# LCLFilter_Top.net
KiCad netlist of a schematic drawn in Altium Designer
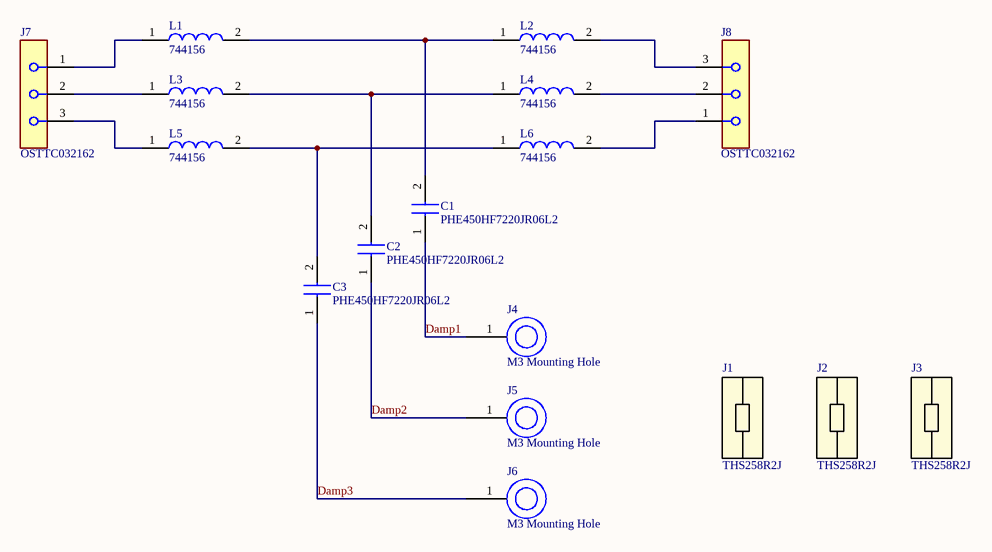
[diagram p0: LCLFilter_Top.SchDoc]

(export (version "E")
  (design (tool "Eeschema 10.0.6"))
  (components
    (comp (ref "C1")
      (value "PHE450HF7220JR06L2")
      (footprint "Film Capacitor PHE450HF7220JR06L2")
      (description "Capacitor")
      (libsource (lib "FYP_Components") (part "PHE450HF7220JR06L2"))
    )
    (comp (ref "C2")
      (value "PHE450HF7220JR06L2")
      (footprint "Film Capacitor PHE450HF7220JR06L2")
      (description "Capacitor")
      (libsource (lib "FYP_Components") (part "PHE450HF7220JR06L2"))
    )
    (comp (ref "C3")
      (value "PHE450HF7220JR06L2")
      (footprint "Film Capacitor PHE450HF7220JR06L2")
      (description "Capacitor")
      (libsource (lib "FYP_Components") (part "PHE450HF7220JR06L2"))
    )
    (comp (ref "J1")
      (value "THS258R2J")
      (footprint "Resistor CONN2_ THS258R2J_TEC")
      (description "Resistor, Axial Leaded, 8.2 ohm, THS, 25 W, ± 5%, Solder Lug, 550 V")
      (fields (field (name "COPYRIGHT") "Copyright (C) 2023 Ultra Librarian. All rights reserved."))
      (libsource (lib "FYP_Components") (part "THS258R2J"))
    )
    (comp (ref "J2")
      (value "THS258R2J")
      (footprint "Resistor CONN2_ THS258R2J_TEC")
      (description "Resistor, Axial Leaded, 8.2 ohm, THS, 25 W, ± 5%, Solder Lug, 550 V")
      (fields (field (name "COPYRIGHT") "Copyright (C) 2023 Ultra Librarian. All rights reserved."))
      (libsource (lib "FYP_Components") (part "THS258R2J"))
    )
    (comp (ref "J3")
      (value "THS258R2J")
      (footprint "Resistor CONN2_ THS258R2J_TEC")
      (description "Resistor, Axial Leaded, 8.2 ohm, THS, 25 W, ± 5%, Solder Lug, 550 V")
      (fields (field (name "COPYRIGHT") "Copyright (C) 2023 Ultra Librarian. All rights reserved."))
      (libsource (lib "FYP_Components") (part "THS258R2J"))
    )
    (comp (ref "J4")
      (value "M3 Mounting Hole")
      (footprint "M3 Mounting Hole")
      (libsource (lib "FYP_Components") (part "M3 Mounting Hole"))
    )
    (comp (ref "J5")
      (value "M3 Mounting Hole")
      (footprint "M3 Mounting Hole")
      (libsource (lib "FYP_Components") (part "M3 Mounting Hole"))
    )
    (comp (ref "J6")
      (value "M3 Mounting Hole")
      (footprint "M3 Mounting Hole")
      (libsource (lib "FYP_Components") (part "M3 Mounting Hole"))
    )
    (comp (ref "J7")
      (value "OSTTC032162")
      (footprint "3 Pin Terminal OSTTC032162_0")
      (description "3 Position Terminal Block 5.08mm")
      (fields
        (field (name "VOLTAGE") "300V")
        (field (name "MANUFACTURER") "On Shore Technology")
        (field (name "PART NUMBER") "OSTTC032162")
      )
      (libsource (lib "FYP_Components") (part "OSTTC032162"))
    )
    (comp (ref "J8")
      (value "OSTTC032162")
      (footprint "3 Pin Terminal OSTTC032162_0")
      (description "3 Position Terminal Block 5.08mm")
      (fields
        (field (name "VOLTAGE") "300V")
        (field (name "MANUFACTURER") "On Shore Technology")
        (field (name "PART NUMBER") "OSTTC032162")
      )
      (libsource (lib "") (part "OSTTC032162_1"))
    )
    (comp (ref "L1")
      (value "744156")
      (footprint "Toroid Inductor 744156")
      (description "Toroidal Inductor, WE-SI, 380 µH, 6.2 A, 0.07 ohm, ± 20%")
      (libsource (lib "FYP_Components") (part "744156"))
    )
    (comp (ref "L2")
      (value "744156")
      (footprint "Toroid Inductor 744156")
      (description "Toroidal Inductor, WE-SI, 380 µH, 6.2 A, 0.07 ohm, ± 20%")
      (libsource (lib "FYP_Components") (part "744156"))
    )
    (comp (ref "L3")
      (value "744156")
      (footprint "Toroid Inductor 744156")
      (description "Toroidal Inductor, WE-SI, 380 µH, 6.2 A, 0.07 ohm, ± 20%")
      (libsource (lib "FYP_Components") (part "744156"))
    )
    (comp (ref "L4")
      (value "744156")
      (footprint "Toroid Inductor 744156")
      (description "Toroidal Inductor, WE-SI, 380 µH, 6.2 A, 0.07 ohm, ± 20%")
      (libsource (lib "FYP_Components") (part "744156"))
    )
    (comp (ref "L5")
      (value "744156")
      (footprint "Toroid Inductor 744156")
      (description "Toroidal Inductor, WE-SI, 380 µH, 6.2 A, 0.07 ohm, ± 20%")
      (libsource (lib "FYP_Components") (part "744156"))
    )
    (comp (ref "L6")
      (value "744156")
      (footprint "Toroid Inductor 744156")
      (description "Toroidal Inductor, WE-SI, 380 µH, 6.2 A, 0.07 ohm, ± 20%")
      (libsource (lib "FYP_Components") (part "744156"))
    )
  )
  (nets
    (net (code "1") (name "/Damp1") (class "Default")
      (node (ref "C1") (pin "1") (pinfunction "1_1") (pintype "passive"))
      (node (ref "J4") (pin "1") (pinfunction "1_1") (pintype "passive"))
    )
    (net (code "2") (name "/Damp2") (class "Default")
      (node (ref "C2") (pin "1") (pinfunction "1_1") (pintype "passive"))
      (node (ref "J5") (pin "1") (pinfunction "1_1") (pintype "passive"))
    )
    (net (code "3") (name "/Damp3") (class "Default")
      (node (ref "C3") (pin "1") (pinfunction "1_1") (pintype "passive"))
      (node (ref "J6") (pin "1") (pinfunction "1_1") (pintype "passive"))
    )
    (net (code "4") (name "Net-(C1-Pad2)") (class "Default")
      (node (ref "C1") (pin "2") (pinfunction "2_2") (pintype "passive"))
      (node (ref "L1") (pin "2") (pinfunction "2_2") (pintype "passive"))
      (node (ref "L2") (pin "1") (pinfunction "1_1") (pintype "passive"))
    )
    (net (code "5") (name "Net-(C2-Pad2)") (class "Default")
      (node (ref "C2") (pin "2") (pinfunction "2_2") (pintype "passive"))
      (node (ref "L3") (pin "2") (pinfunction "2_2") (pintype "passive"))
      (node (ref "L4") (pin "1") (pinfunction "1_1") (pintype "passive"))
    )
    (net (code "6") (name "Net-(C3-Pad2)") (class "Default")
      (node (ref "C3") (pin "2") (pinfunction "2_2") (pintype "passive"))
      (node (ref "L5") (pin "2") (pinfunction "2_2") (pintype "passive"))
      (node (ref "L6") (pin "1") (pinfunction "1_1") (pintype "passive"))
    )
    (net (code "7") (name "Net-(J7-Pad1)") (class "Default")
      (node (ref "J7") (pin "1") (pinfunction "1_1") (pintype "passive"))
      (node (ref "L1") (pin "1") (pinfunction "1_1") (pintype "passive"))
    )
    (net (code "8") (name "Net-(J7-Pad2)") (class "Default")
      (node (ref "J7") (pin "2") (pinfunction "2_2") (pintype "passive"))
      (node (ref "L3") (pin "1") (pinfunction "1_1") (pintype "passive"))
    )
    (net (code "9") (name "Net-(J7-Pad3)") (class "Default")
      (node (ref "J7") (pin "3") (pinfunction "3_3") (pintype "passive"))
      (node (ref "L5") (pin "1") (pinfunction "1_1") (pintype "passive"))
    )
    (net (code "10") (name "Net-(J8-Pad1)") (class "Default")
      (node (ref "J8") (pin "1") (pinfunction "1_1") (pintype "passive"))
      (node (ref "L6") (pin "2") (pinfunction "2_2") (pintype "passive"))
    )
    (net (code "11") (name "Net-(J8-Pad2)") (class "Default")
      (node (ref "J8") (pin "2") (pinfunction "2_2") (pintype "passive"))
      (node (ref "L4") (pin "2") (pinfunction "2_2") (pintype "passive"))
    )
    (net (code "12") (name "Net-(J8-Pad3)") (class "Default")
      (node (ref "J8") (pin "3") (pinfunction "3_3") (pintype "passive"))
      (node (ref "L2") (pin "2") (pinfunction "2_2") (pintype "passive"))
    )
  )
)
